# connectors.net
KiCad netlist of a schematic drawn in EAGLE
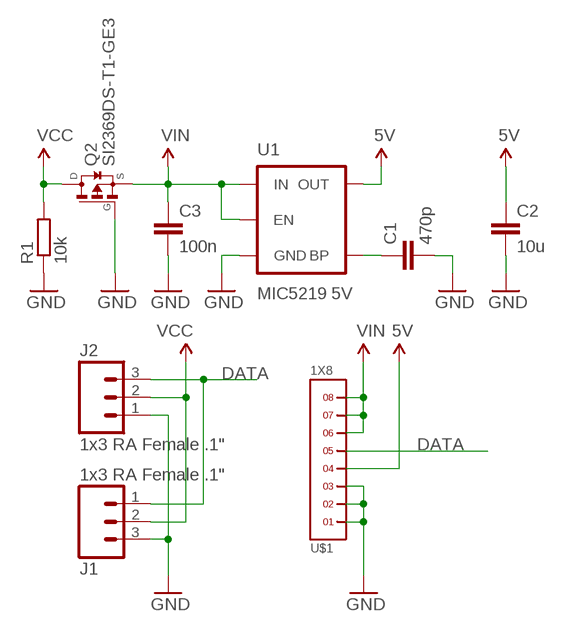
[diagram p0: schematic, sheet 1]

(export (version "E")
  (design (tool "Eeschema 10.0.6"))
  (components
    (comp (ref "C1")
      (value "470p")
      (footprint "eagle-import:C0402K")
      (libsource (lib "eagle-import") (part "C-EUC0402K"))
    )
    (comp (ref "C2")
      (value "10u")
      (footprint "eagle-import:C0603K")
      (libsource (lib "eagle-import") (part "C-EUC0603K"))
    )
    (comp (ref "C3")
      (value "100n")
      (footprint "eagle-import:C0402K")
      (libsource (lib "eagle-import") (part "C-EUC0402K"))
    )
    (comp (ref "J1")
      (value "1x3 RA Female .1\"")
      (footprint "eagle-import:1X03_SMD_RA_FEMALE")
      (libsource (lib "eagle-import") (part "M03SMD_RA_FEMALE"))
    )
    (comp (ref "J2")
      (value "1x3 RA Female .1\"")
      (footprint "eagle-import:1X03_SMD_RA_FEMALE")
      (libsource (lib "eagle-import") (part "M03SMD_RA_FEMALE"))
    )
    (comp (ref "Q2")
      (value "SI2369DS-T1-GE3")
      (footprint "eagle-import:SOT23")
      (libsource (lib "eagle-import") (part "SI2333DS"))
    )
    (comp (ref "R1")
      (value "10k")
      (footprint "eagle-import:R0603")
      (libsource (lib "eagle-import") (part "R-EU_R0603"))
    )
    (comp (ref "U$1")
      (value "1X8")
      (footprint "eagle-import:1X8")
      (libsource (lib "eagle-import") (part "1X8"))
    )
    (comp (ref "U1")
      (value "MIC5219 5V")
      (footprint "eagle-import:SOT23-5")
      (libsource (lib "eagle-import") (part "V_REG_MIC52195V"))
    )
  )
  (nets
    (net (code "1") (name "/DATA") (class "Default")
      (node (ref "J1") (pin "1") (pinfunction "1_1") (pintype "passive"))
      (node (ref "J2") (pin "3") (pinfunction "3_3") (pintype "passive"))
      (node (ref "U$1") (pin "5") (pinfunction "5_5") (pintype "bidirectional"))
    )
    (net (code "2") (name "5V") (class "Default")
      (node (ref "C2") (pin "1") (pinfunction "1_1") (pintype "passive"))
      (node (ref "U$1") (pin "4") (pinfunction "4_4") (pintype "bidirectional"))
      (node (ref "U1") (pin "5") (pinfunction "OUT_5") (pintype "passive"))
    )
    (net (code "3") (name "GND") (class "Default")
      (node (ref "C1") (pin "2") (pinfunction "2_2") (pintype "passive"))
      (node (ref "C2") (pin "2") (pinfunction "2_2") (pintype "passive"))
      (node (ref "C3") (pin "2") (pinfunction "2_2") (pintype "passive"))
      (node (ref "J1") (pin "3") (pinfunction "3_3") (pintype "passive"))
      (node (ref "J2") (pin "1") (pinfunction "1_1") (pintype "passive"))
      (node (ref "Q2") (pin "1") (pinfunction "G_1") (pintype "passive"))
      (node (ref "R1") (pin "1") (pinfunction "1_1") (pintype "passive"))
      (node (ref "U$1") (pin "1") (pinfunction "1_1") (pintype "bidirectional"))
      (node (ref "U$1") (pin "2") (pinfunction "2_2") (pintype "bidirectional"))
      (node (ref "U$1") (pin "3") (pinfunction "3_3") (pintype "bidirectional"))
      (node (ref "U1") (pin "2") (pinfunction "GND_2") (pintype "input"))
    )
    (net (code "4") (name "Net-(U1-BP)") (class "Default")
      (node (ref "C1") (pin "1") (pinfunction "1_1") (pintype "passive"))
      (node (ref "U1") (pin "4") (pinfunction "BP_4") (pintype "input"))
    )
    (net (code "5") (name "VCC") (class "Default")
      (node (ref "J1") (pin "2") (pinfunction "2_2") (pintype "passive"))
      (node (ref "J2") (pin "2") (pinfunction "2_2") (pintype "passive"))
      (node (ref "Q2") (pin "3") (pinfunction "D_3") (pintype "passive"))
      (node (ref "R1") (pin "2") (pinfunction "2_2") (pintype "passive"))
    )
    (net (code "6") (name "VIN") (class "Default")
      (node (ref "C3") (pin "1") (pinfunction "1_1") (pintype "passive"))
      (node (ref "Q2") (pin "2") (pinfunction "S_2") (pintype "passive"))
      (node (ref "U$1") (pin "6") (pinfunction "6_6") (pintype "bidirectional"))
      (node (ref "U$1") (pin "7") (pinfunction "7_7") (pintype "bidirectional"))
      (node (ref "U$1") (pin "8") (pinfunction "8_8") (pintype "bidirectional"))
      (node (ref "U1") (pin "1") (pinfunction "IN_1") (pintype "input"))
      (node (ref "U1") (pin "3") (pinfunction "EN_3") (pintype "input"))
    )
  )
)
